# ou6_cs-base_V1_1.net
KiCad netlist of a schematic drawn in EAGLE
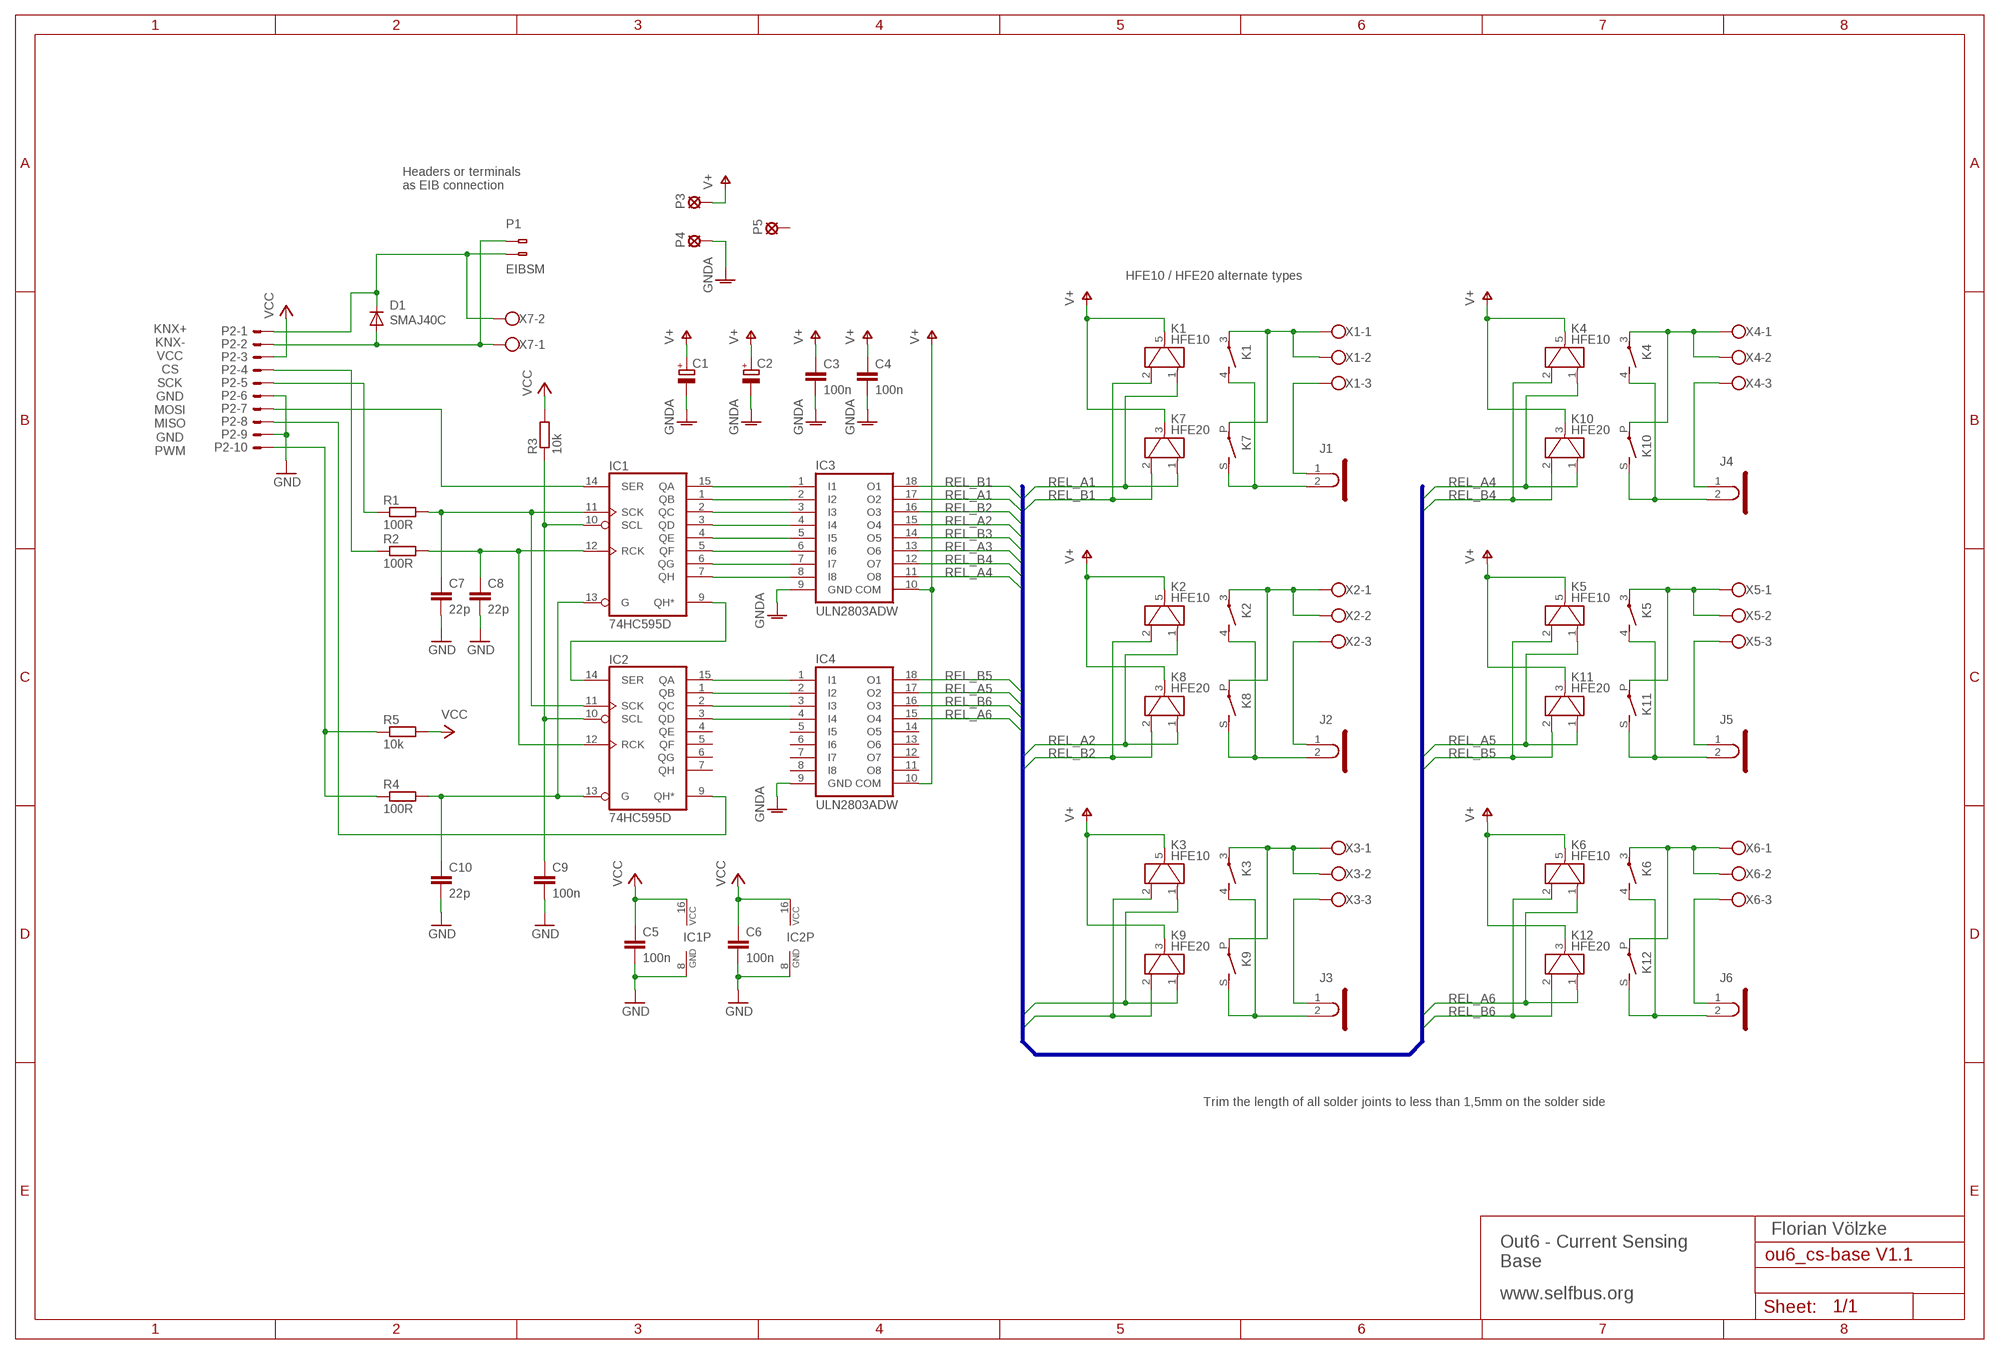
[diagram p0: schematic, sheet 1]

(export (version "E")
  (design (tool "Eeschema 10.0.6"))
  (components
    (comp (ref "C1")
      (value "CPOL-EUE5-13-20")
      (footprint "eagle-import:E5-13-20")
      (libsource (lib "eagle-import") (part "CPOL-EUE5-13-20"))
    )
    (comp (ref "C2")
      (value "CPOL-EUE5-13-20R")
      (footprint "eagle-import:E5-13-20R")
      (libsource (lib "eagle-import") (part "CPOL-EUE5-13-20R"))
    )
    (comp (ref "C3")
      (value "100n")
      (footprint "eagle-import:R0805M")
      (libsource (lib "eagle-import") (part "C-EUC0805M"))
    )
    (comp (ref "C4")
      (value "100n")
      (footprint "eagle-import:R0805M")
      (libsource (lib "eagle-import") (part "C-EUC0805M"))
    )
    (comp (ref "C5")
      (value "100n")
      (footprint "eagle-import:R0805M")
      (libsource (lib "eagle-import") (part "C-EUC0805M"))
    )
    (comp (ref "C6")
      (value "100n")
      (footprint "eagle-import:R0805M")
      (libsource (lib "eagle-import") (part "C-EUC0805M"))
    )
    (comp (ref "C7")
      (value "22p")
      (footprint "eagle-import:R0805M")
      (libsource (lib "eagle-import") (part "C-EUC0805M"))
    )
    (comp (ref "C8")
      (value "22p")
      (footprint "eagle-import:R0805M")
      (libsource (lib "eagle-import") (part "C-EUC0805M"))
    )
    (comp (ref "C9")
      (value "100n")
      (footprint "eagle-import:R0805M")
      (libsource (lib "eagle-import") (part "C-EUC0805M"))
    )
    (comp (ref "C10")
      (value "22p")
      (footprint "eagle-import:R0805M")
      (libsource (lib "eagle-import") (part "C-EUC0805M"))
    )
    (comp (ref "D1")
      (value "SMAJ40C")
      (footprint "eagle-import:SMB")
      (libsource (lib "eagle-import") (part "D-SMB"))
    )
    (comp (ref "IC1")
      (value "74HC595D")
      (footprint "eagle-import:SO16")
      (libsource (lib "eagle-import") (part "74595DHC"))
    )
    (comp (ref "IC2")
      (value "74HC595D")
      (footprint "eagle-import:SO16")
      (libsource (lib "eagle-import") (part "74595DHC"))
    )
    (comp (ref "IC3")
      (value "ULN2803ADW")
      (footprint "eagle-import:SO18W")
      (libsource (lib "eagle-import") (part "ULN2803ADW"))
    )
    (comp (ref "IC4")
      (value "ULN2803ADW")
      (footprint "eagle-import:SO18W")
      (libsource (lib "eagle-import") (part "ULN2803ADW"))
    )
    (comp (ref "J1")
      (value "IXFORMER_PRIMONLY")
      (footprint "eagle-import:IXFORMERANTIPART")
      (libsource (lib "eagle-import") (part "IXFORMER_PRIMONLY"))
    )
    (comp (ref "J2")
      (value "IXFORMER_PRIMONLY")
      (footprint "eagle-import:IXFORMERANTIPART")
      (libsource (lib "eagle-import") (part "IXFORMER_PRIMONLY"))
    )
    (comp (ref "J3")
      (value "IXFORMER_PRIMONLY")
      (footprint "eagle-import:IXFORMERANTIPART")
      (libsource (lib "eagle-import") (part "IXFORMER_PRIMONLY"))
    )
    (comp (ref "J4")
      (value "IXFORMER_PRIMONLY")
      (footprint "eagle-import:IXFORMERANTIPART")
      (libsource (lib "eagle-import") (part "IXFORMER_PRIMONLY"))
    )
    (comp (ref "J5")
      (value "IXFORMER_PRIMONLY")
      (footprint "eagle-import:IXFORMERANTIPART")
      (libsource (lib "eagle-import") (part "IXFORMER_PRIMONLY"))
    )
    (comp (ref "J6")
      (value "IXFORMER_PRIMONLY")
      (footprint "eagle-import:IXFORMERANTIPART")
      (libsource (lib "eagle-import") (part "IXFORMER_PRIMONLY"))
    )
    (comp (ref "K1")
      (value "HFE10")
      (footprint "eagle-import:PCB_REL_BIG_POWER_NO")
      (libsource (lib "eagle-import") (part "BISTABLE2C_PCB_SNGLPINHFE10"))
    )
    (comp (ref "K2")
      (value "HFE10")
      (footprint "eagle-import:PCB_REL_BIG_POWER_NO")
      (libsource (lib "eagle-import") (part "BISTABLE2C_PCB_SNGLPINHFE10"))
    )
    (comp (ref "K3")
      (value "HFE10")
      (footprint "eagle-import:PCB_REL_BIG_POWER_NO")
      (libsource (lib "eagle-import") (part "BISTABLE2C_PCB_SNGLPINHFE10"))
    )
    (comp (ref "K4")
      (value "HFE10")
      (footprint "eagle-import:PCB_REL_BIG_POWER_NO")
      (libsource (lib "eagle-import") (part "BISTABLE2C_PCB_SNGLPINHFE10"))
    )
    (comp (ref "K5")
      (value "HFE10")
      (footprint "eagle-import:PCB_REL_BIG_POWER_NO")
      (libsource (lib "eagle-import") (part "BISTABLE2C_PCB_SNGLPINHFE10"))
    )
    (comp (ref "K6")
      (value "HFE10")
      (footprint "eagle-import:PCB_REL_BIG_POWER_NO")
      (libsource (lib "eagle-import") (part "BISTABLE2C_PCB_SNGLPINHFE10"))
    )
    (comp (ref "K7")
      (value "HFE20")
      (footprint "eagle-import:PCB_REL_HP_NO_SNGLPIN")
      (libsource (lib "eagle-import") (part "BISTABLE2C_PCB_SNGLPINHFE20"))
    )
    (comp (ref "K8")
      (value "HFE20")
      (footprint "eagle-import:PCB_REL_HP_NO_SNGLPIN")
      (libsource (lib "eagle-import") (part "BISTABLE2C_PCB_SNGLPINHFE20"))
    )
    (comp (ref "K9")
      (value "HFE20")
      (footprint "eagle-import:PCB_REL_HP_NO_SNGLPIN")
      (libsource (lib "eagle-import") (part "BISTABLE2C_PCB_SNGLPINHFE20"))
    )
    (comp (ref "K10")
      (value "HFE20")
      (footprint "eagle-import:PCB_REL_HP_NO_SNGLPIN")
      (libsource (lib "eagle-import") (part "BISTABLE2C_PCB_SNGLPINHFE20"))
    )
    (comp (ref "K11")
      (value "HFE20")
      (footprint "eagle-import:PCB_REL_HP_NO_SNGLPIN")
      (libsource (lib "eagle-import") (part "BISTABLE2C_PCB_SNGLPINHFE20"))
    )
    (comp (ref "K12")
      (value "HFE20")
      (footprint "eagle-import:PCB_REL_HP_NO_SNGLPIN")
      (libsource (lib "eagle-import") (part "BISTABLE2C_PCB_SNGLPINHFE20"))
    )
    (comp (ref "P1")
      (value "EIBSM")
      (footprint "eagle-import:BUSKLEMME1_2LOECHER")
      (libsource (lib "eagle-import") (part "EIBSM"))
    )
    (comp (ref "P2")
      (value "ML10E")
      (footprint "eagle-import:ML10")
      (libsource (lib "eagle-import") (part "ML10?E"))
    )
    (comp (ref "P3")
      (value "SE1.5")
      (footprint "eagle-import:SE15")
      (libsource (lib "eagle-import") (part "SE1.5"))
    )
    (comp (ref "P4")
      (value "SE1.5")
      (footprint "eagle-import:SE15")
      (libsource (lib "eagle-import") (part "SE1.5"))
    )
    (comp (ref "P5")
      (value "SE1.5")
      (footprint "eagle-import:SE15")
      (libsource (lib "eagle-import") (part "SE1.5"))
    )
    (comp (ref "R1")
      (value "100R")
      (footprint "eagle-import:R0805M")
      (libsource (lib "eagle-import") (part "R-EU_R0805M"))
    )
    (comp (ref "R2")
      (value "100R")
      (footprint "eagle-import:R0805M")
      (libsource (lib "eagle-import") (part "R-EU_R0805M"))
    )
    (comp (ref "R3")
      (value "10k")
      (footprint "eagle-import:R0805M")
      (libsource (lib "eagle-import") (part "R-EU_R0805M"))
    )
    (comp (ref "R4")
      (value "100R")
      (footprint "eagle-import:R0805M")
      (libsource (lib "eagle-import") (part "R-EU_R0805M"))
    )
    (comp (ref "R5")
      (value "10k")
      (footprint "eagle-import:R0805M")
      (libsource (lib "eagle-import") (part "R-EU_R0805M"))
    )
    (comp (ref "X1")
      (value "KLEMME3POL5_08")
      (footprint "eagle-import:KLEMME3POL5_08")
      (libsource (lib "eagle-import") (part "KLEMME3POL5_08"))
    )
    (comp (ref "X2")
      (value "KLEMME3POL5_08")
      (footprint "eagle-import:KLEMME3POL5_08")
      (libsource (lib "eagle-import") (part "KLEMME3POL5_08"))
    )
    (comp (ref "X3")
      (value "KLEMME3POL5_08")
      (footprint "eagle-import:KLEMME3POL5_08")
      (libsource (lib "eagle-import") (part "KLEMME3POL5_08"))
    )
    (comp (ref "X4")
      (value "KLEMME3POL5_08")
      (footprint "eagle-import:KLEMME3POL5_08")
      (libsource (lib "eagle-import") (part "KLEMME3POL5_08"))
    )
    (comp (ref "X5")
      (value "KLEMME3POL5_08")
      (footprint "eagle-import:KLEMME3POL5_08")
      (libsource (lib "eagle-import") (part "KLEMME3POL5_08"))
    )
    (comp (ref "X6")
      (value "KLEMME3POL5_08")
      (footprint "eagle-import:KLEMME3POL5_08")
      (libsource (lib "eagle-import") (part "KLEMME3POL5_08"))
    )
    (comp (ref "X7")
      (value "KLEMME2POL5_08")
      (footprint "eagle-import:KLEMME2POL5_08")
      (libsource (lib "eagle-import") (part "KLEMME2POL5_08"))
    )
  )
  (nets
    (net (code "1") (name "/REL_A1") (class "Default")
      (node (ref "IC3") (pin "17") (pinfunction "O2_17") (pintype "open_collector"))
      (node (ref "K1") (pin "1") (pinfunction "3_1") (pintype "passive"))
      (node (ref "K7") (pin "1") (pinfunction "3_1") (pintype "passive"))
    )
    (net (code "2") (name "/REL_A2") (class "Default")
      (node (ref "IC3") (pin "15") (pinfunction "O4_15") (pintype "open_collector"))
      (node (ref "K2") (pin "1") (pinfunction "3_1") (pintype "passive"))
      (node (ref "K8") (pin "1") (pinfunction "3_1") (pintype "passive"))
    )
    (net (code "3") (name "/REL_A3") (class "Default")
      (node (ref "IC3") (pin "13") (pinfunction "O6_13") (pintype "open_collector"))
      (node (ref "K3") (pin "1") (pinfunction "3_1") (pintype "passive"))
      (node (ref "K9") (pin "1") (pinfunction "3_1") (pintype "passive"))
    )
    (net (code "4") (name "/REL_A4") (class "Default")
      (node (ref "IC3") (pin "11") (pinfunction "O8_11") (pintype "open_collector"))
      (node (ref "K10") (pin "1") (pinfunction "3_1") (pintype "passive"))
      (node (ref "K4") (pin "1") (pinfunction "3_1") (pintype "passive"))
    )
    (net (code "5") (name "/REL_A5") (class "Default")
      (node (ref "IC4") (pin "17") (pinfunction "O2_17") (pintype "open_collector"))
      (node (ref "K11") (pin "1") (pinfunction "3_1") (pintype "passive"))
      (node (ref "K5") (pin "1") (pinfunction "3_1") (pintype "passive"))
    )
    (net (code "6") (name "/REL_A6") (class "Default")
      (node (ref "IC4") (pin "15") (pinfunction "O4_15") (pintype "open_collector"))
      (node (ref "K12") (pin "1") (pinfunction "3_1") (pintype "passive"))
      (node (ref "K6") (pin "1") (pinfunction "3_1") (pintype "passive"))
    )
    (net (code "7") (name "/REL_B1") (class "Default")
      (node (ref "IC3") (pin "18") (pinfunction "O1_18") (pintype "open_collector"))
      (node (ref "K1") (pin "2") (pinfunction "2_2") (pintype "passive"))
      (node (ref "K7") (pin "2") (pinfunction "2_2") (pintype "passive"))
    )
    (net (code "8") (name "/REL_B2") (class "Default")
      (node (ref "IC3") (pin "16") (pinfunction "O3_16") (pintype "open_collector"))
      (node (ref "K2") (pin "2") (pinfunction "2_2") (pintype "passive"))
      (node (ref "K8") (pin "2") (pinfunction "2_2") (pintype "passive"))
    )
    (net (code "9") (name "/REL_B3") (class "Default")
      (node (ref "IC3") (pin "14") (pinfunction "O5_14") (pintype "open_collector"))
      (node (ref "K3") (pin "2") (pinfunction "2_2") (pintype "passive"))
      (node (ref "K9") (pin "2") (pinfunction "2_2") (pintype "passive"))
    )
    (net (code "10") (name "/REL_B4") (class "Default")
      (node (ref "IC3") (pin "12") (pinfunction "O7_12") (pintype "open_collector"))
      (node (ref "K10") (pin "2") (pinfunction "2_2") (pintype "passive"))
      (node (ref "K4") (pin "2") (pinfunction "2_2") (pintype "passive"))
    )
    (net (code "11") (name "/REL_B5") (class "Default")
      (node (ref "IC4") (pin "18") (pinfunction "O1_18") (pintype "open_collector"))
      (node (ref "K11") (pin "2") (pinfunction "2_2") (pintype "passive"))
      (node (ref "K5") (pin "2") (pinfunction "2_2") (pintype "passive"))
    )
    (net (code "12") (name "/REL_B6") (class "Default")
      (node (ref "IC4") (pin "16") (pinfunction "O3_16") (pintype "open_collector"))
      (node (ref "K12") (pin "2") (pinfunction "2_2") (pintype "passive"))
      (node (ref "K6") (pin "2") (pinfunction "2_2") (pintype "passive"))
    )
    (net (code "13") (name "GND") (class "Default")
      (node (ref "C10") (pin "2") (pinfunction "2_2") (pintype "passive"))
      (node (ref "C5") (pin "2") (pinfunction "2_2") (pintype "passive"))
      (node (ref "C6") (pin "2") (pinfunction "2_2") (pintype "passive"))
      (node (ref "C7") (pin "2") (pinfunction "2_2") (pintype "passive"))
      (node (ref "C8") (pin "2") (pinfunction "2_2") (pintype "passive"))
      (node (ref "C9") (pin "2") (pinfunction "2_2") (pintype "passive"))
      (node (ref "IC1") (pin "8") (pinfunction "GND_8") (pintype "power_in"))
      (node (ref "IC2") (pin "8") (pinfunction "GND_8") (pintype "power_in"))
      (node (ref "P2") (pin "6") (pinfunction "S_6") (pintype "passive"))
      (node (ref "P2") (pin "9") (pinfunction "S_9") (pintype "passive"))
    )
    (net (code "14") (name "GNDA") (class "Default")
      (node (ref "C1") (pin "-") (pinfunction "-_-") (pintype "passive"))
      (node (ref "C2") (pin "-") (pinfunction "-_-") (pintype "passive"))
      (node (ref "C3") (pin "2") (pinfunction "2_2") (pintype "passive"))
      (node (ref "C4") (pin "2") (pinfunction "2_2") (pintype "passive"))
      (node (ref "IC3") (pin "9") (pinfunction "GND_9") (pintype "power_in"))
      (node (ref "IC4") (pin "9") (pinfunction "GND_9") (pintype "power_in"))
      (node (ref "P4") (pin "MP") (pinfunction "MP_MP") (pintype "passive"))
    )
    (net (code "15") (name "Net-(D1-A)") (class "Default")
      (node (ref "D1") (pin "2") (pinfunction "A_2") (pintype "passive"))
      (node (ref "P1") (pin "1") (pinfunction "B-1_1") (pintype "passive"))
      (node (ref "P2") (pin "2") (pinfunction "S_2") (pintype "passive"))
      (node (ref "X7") (pin "P$1") (pinfunction "KL_P$1") (pintype "passive"))
    )
    (net (code "16") (name "Net-(D1-C)") (class "Default")
      (node (ref "D1") (pin "1") (pinfunction "C_1") (pintype "passive"))
      (node (ref "P1") (pin "2") (pinfunction "B-2_2") (pintype "passive"))
      (node (ref "P2") (pin "1") (pinfunction "S_1") (pintype "passive"))
      (node (ref "X7") (pin "P$2") (pinfunction "KL_P$2") (pintype "passive"))
    )
    (net (code "17") (name "Net-(IC1A-G)") (class "Default")
      (node (ref "C10") (pin "1") (pinfunction "1_1") (pintype "passive"))
      (node (ref "IC1") (pin "13") (pinfunction "G_13") (pintype "input"))
      (node (ref "IC2") (pin "13") (pinfunction "G_13") (pintype "input"))
      (node (ref "R4") (pin "2") (pinfunction "2_2") (pintype "passive"))
    )
    (net (code "18") (name "Net-(IC1A-QA)") (class "Default")
      (node (ref "IC1") (pin "15") (pinfunction "QA_15") (pintype "tri_state"))
      (node (ref "IC3") (pin "1") (pinfunction "I1_1") (pintype "input"))
    )
    (net (code "19") (name "Net-(IC1A-QB)") (class "Default")
      (node (ref "IC1") (pin "1") (pinfunction "QB_1") (pintype "tri_state"))
      (node (ref "IC3") (pin "2") (pinfunction "I2_2") (pintype "input"))
    )
    (net (code "20") (name "Net-(IC1A-QC)") (class "Default")
      (node (ref "IC1") (pin "2") (pinfunction "QC_2") (pintype "tri_state"))
      (node (ref "IC3") (pin "3") (pinfunction "I3_3") (pintype "input"))
    )
    (net (code "21") (name "Net-(IC1A-QD)") (class "Default")
      (node (ref "IC1") (pin "3") (pinfunction "QD_3") (pintype "tri_state"))
      (node (ref "IC3") (pin "4") (pinfunction "I4_4") (pintype "input"))
    )
    (net (code "22") (name "Net-(IC1A-QE)") (class "Default")
      (node (ref "IC1") (pin "4") (pinfunction "QE_4") (pintype "tri_state"))
      (node (ref "IC3") (pin "5") (pinfunction "I5_5") (pintype "input"))
    )
    (net (code "23") (name "Net-(IC1A-QF)") (class "Default")
      (node (ref "IC1") (pin "5") (pinfunction "QF_5") (pintype "tri_state"))
      (node (ref "IC3") (pin "6") (pinfunction "I6_6") (pintype "input"))
    )
    (net (code "24") (name "Net-(IC1A-QG)") (class "Default")
      (node (ref "IC1") (pin "6") (pinfunction "QG_6") (pintype "tri_state"))
      (node (ref "IC3") (pin "7") (pinfunction "I7_7") (pintype "input"))
    )
    (net (code "25") (name "Net-(IC1A-QH)") (class "Default")
      (node (ref "IC1") (pin "7") (pinfunction "QH_7") (pintype "tri_state"))
      (node (ref "IC3") (pin "8") (pinfunction "I8_8") (pintype "input"))
    )
    (net (code "26") (name "Net-(IC1A-QH*)") (class "Default")
      (node (ref "IC1") (pin "9") (pinfunction "QH*_9") (pintype "tri_state"))
      (node (ref "IC2") (pin "14") (pinfunction "SER_14") (pintype "input"))
    )
    (net (code "27") (name "Net-(IC1A-RCK)") (class "Default")
      (node (ref "C8") (pin "1") (pinfunction "1_1") (pintype "passive"))
      (node (ref "IC1") (pin "12") (pinfunction "RCK_12") (pintype "input"))
      (node (ref "IC2") (pin "12") (pinfunction "RCK_12") (pintype "input"))
      (node (ref "R2") (pin "2") (pinfunction "2_2") (pintype "passive"))
    )
    (net (code "28") (name "Net-(IC1A-SCK)") (class "Default")
      (node (ref "C7") (pin "1") (pinfunction "1_1") (pintype "passive"))
      (node (ref "IC1") (pin "11") (pinfunction "SCK_11") (pintype "input"))
      (node (ref "IC2") (pin "11") (pinfunction "SCK_11") (pintype "input"))
      (node (ref "R1") (pin "2") (pinfunction "2_2") (pintype "passive"))
    )
    (net (code "29") (name "Net-(IC1A-SCL)") (class "Default")
      (node (ref "C9") (pin "1") (pinfunction "1_1") (pintype "passive"))
      (node (ref "IC1") (pin "10") (pinfunction "SCL_10") (pintype "input"))
      (node (ref "IC2") (pin "10") (pinfunction "SCL_10") (pintype "input"))
      (node (ref "R3") (pin "1") (pinfunction "1_1") (pintype "passive"))
    )
    (net (code "30") (name "Net-(IC1A-SER)") (class "Default")
      (node (ref "IC1") (pin "14") (pinfunction "SER_14") (pintype "input"))
      (node (ref "P2") (pin "7") (pinfunction "S_7") (pintype "passive"))
    )
    (net (code "31") (name "Net-(IC2A-QA)") (class "Default")
      (node (ref "IC2") (pin "15") (pinfunction "QA_15") (pintype "tri_state"))
      (node (ref "IC4") (pin "1") (pinfunction "I1_1") (pintype "input"))
    )
    (net (code "32") (name "Net-(IC2A-QB)") (class "Default")
      (node (ref "IC2") (pin "1") (pinfunction "QB_1") (pintype "tri_state"))
      (node (ref "IC4") (pin "2") (pinfunction "I2_2") (pintype "input"))
    )
    (net (code "33") (name "Net-(IC2A-QC)") (class "Default")
      (node (ref "IC2") (pin "2") (pinfunction "QC_2") (pintype "tri_state"))
      (node (ref "IC4") (pin "3") (pinfunction "I3_3") (pintype "input"))
    )
    (net (code "34") (name "Net-(IC2A-QD)") (class "Default")
      (node (ref "IC2") (pin "3") (pinfunction "QD_3") (pintype "tri_state"))
      (node (ref "IC4") (pin "4") (pinfunction "I4_4") (pintype "input"))
    )
    (net (code "35") (name "Net-(IC2A-QH*)") (class "Default")
      (node (ref "IC2") (pin "9") (pinfunction "QH*_9") (pintype "tri_state"))
      (node (ref "P2") (pin "8") (pinfunction "S_8") (pintype "passive"))
    )
    (net (code "36") (name "Net-(K1B-P)") (class "Default")
      (node (ref "K1") (pin "3") (pinfunction "P_3") (pintype "passive"))
      (node (ref "K7") (pin "P") (pinfunction "P_P") (pintype "passive"))
      (node (ref "X1") (pin "P$1") (pinfunction "KL_P$1") (pintype "passive"))
      (node (ref "X1") (pin "P$2") (pinfunction "KL_P$2") (pintype "passive"))
    )
    (net (code "37") (name "Net-(K1B-S)") (class "Default")
      (node (ref "J1") (pin "2") (pinfunction "2_2") (pintype "passive"))
      (node (ref "K1") (pin "4") (pinfunction "S_4") (pintype "passive"))
      (node (ref "K7") (pin "S") (pinfunction "S_S") (pintype "passive"))
    )
    (net (code "38") (name "Net-(K2B-P)") (class "Default")
      (node (ref "K2") (pin "3") (pinfunction "P_3") (pintype "passive"))
      (node (ref "K8") (pin "P") (pinfunction "P_P") (pintype "passive"))
      (node (ref "X2") (pin "P$1") (pinfunction "KL_P$1") (pintype "passive"))
      (node (ref "X2") (pin "P$2") (pinfunction "KL_P$2") (pintype "passive"))
    )
    (net (code "39") (name "Net-(K2B-S)") (class "Default")
      (node (ref "J2") (pin "2") (pinfunction "2_2") (pintype "passive"))
      (node (ref "K2") (pin "4") (pinfunction "S_4") (pintype "passive"))
      (node (ref "K8") (pin "S") (pinfunction "S_S") (pintype "passive"))
    )
    (net (code "40") (name "Net-(K3B-P)") (class "Default")
      (node (ref "K3") (pin "3") (pinfunction "P_3") (pintype "passive"))
      (node (ref "K9") (pin "P") (pinfunction "P_P") (pintype "passive"))
      (node (ref "X3") (pin "P$1") (pinfunction "KL_P$1") (pintype "passive"))
      (node (ref "X3") (pin "P$2") (pinfunction "KL_P$2") (pintype "passive"))
    )
    (net (code "41") (name "Net-(K3B-S)") (class "Default")
      (node (ref "J3") (pin "2") (pinfunction "2_2") (pintype "passive"))
      (node (ref "K3") (pin "4") (pinfunction "S_4") (pintype "passive"))
      (node (ref "K9") (pin "S") (pinfunction "S_S") (pintype "passive"))
    )
    (net (code "42") (name "Net-(K4B-P)") (class "Default")
      (node (ref "K10") (pin "P") (pinfunction "P_P") (pintype "passive"))
      (node (ref "K4") (pin "3") (pinfunction "P_3") (pintype "passive"))
      (node (ref "X4") (pin "P$1") (pinfunction "KL_P$1") (pintype "passive"))
      (node (ref "X4") (pin "P$2") (pinfunction "KL_P$2") (pintype "passive"))
    )
    (net (code "43") (name "Net-(K4B-S)") (class "Default")
      (node (ref "J4") (pin "2") (pinfunction "2_2") (pintype "passive"))
      (node (ref "K10") (pin "S") (pinfunction "S_S") (pintype "passive"))
      (node (ref "K4") (pin "4") (pinfunction "S_4") (pintype "passive"))
    )
    (net (code "44") (name "Net-(K5B-P)") (class "Default")
      (node (ref "K11") (pin "P") (pinfunction "P_P") (pintype "passive"))
      (node (ref "K5") (pin "3") (pinfunction "P_3") (pintype "passive"))
      (node (ref "X5") (pin "P$1") (pinfunction "KL_P$1") (pintype "passive"))
      (node (ref "X5") (pin "P$2") (pinfunction "KL_P$2") (pintype "passive"))
    )
    (net (code "45") (name "Net-(K5B-S)") (class "Default")
      (node (ref "J5") (pin "2") (pinfunction "2_2") (pintype "passive"))
      (node (ref "K11") (pin "S") (pinfunction "S_S") (pintype "passive"))
      (node (ref "K5") (pin "4") (pinfunction "S_4") (pintype "passive"))
    )
    (net (code "46") (name "Net-(K6B-P)") (class "Default")
      (node (ref "K12") (pin "P") (pinfunction "P_P") (pintype "passive"))
      (node (ref "K6") (pin "3") (pinfunction "P_3") (pintype "passive"))
      (node (ref "X6") (pin "P$1") (pinfunction "KL_P$1") (pintype "passive"))
      (node (ref "X6") (pin "P$2") (pinfunction "KL_P$2") (pintype "passive"))
    )
    (net (code "47") (name "Net-(K6B-S)") (class "Default")
      (node (ref "J6") (pin "2") (pinfunction "2_2") (pintype "passive"))
      (node (ref "K12") (pin "S") (pinfunction "S_S") (pintype "passive"))
      (node (ref "K6") (pin "4") (pinfunction "S_4") (pintype "passive"))
    )
    (net (code "48") (name "Net-(P2B-S)") (class "Default")
      (node (ref "P2") (pin "10") (pinfunction "S_10") (pintype "passive"))
      (node (ref "R4") (pin "1") (pinfunction "1_1") (pintype "passive"))
      (node (ref "R5") (pin "1") (pinfunction "1_1") (pintype "passive"))
    )
    (net (code "49") (name "Net-(P2E-S)") (class "Default")
      (node (ref "P2") (pin "4") (pinfunction "S_4") (pintype "passive"))
      (node (ref "R2") (pin "1") (pinfunction "1_1") (pintype "passive"))
    )
    (net (code "50") (name "Net-(P2F-S)") (class "Default")
      (node (ref "P2") (pin "5") (pinfunction "S_5") (pintype "passive"))
      (node (ref "R1") (pin "1") (pinfunction "1_1") (pintype "passive"))
    )
    (net (code "51") (name "Net-(X1C-KL)") (class "Default")
      (node (ref "J1") (pin "1") (pinfunction "1_1") (pintype "passive"))
      (node (ref "X1") (pin "P$3") (pinfunction "KL_P$3") (pintype "passive"))
    )
    (net (code "52") (name "Net-(X2C-KL)") (class "Default")
      (node (ref "J2") (pin "1") (pinfunction "1_1") (pintype "passive"))
      (node (ref "X2") (pin "P$3") (pinfunction "KL_P$3") (pintype "passive"))
    )
    (net (code "53") (name "Net-(X3C-KL)") (class "Default")
      (node (ref "J3") (pin "1") (pinfunction "1_1") (pintype "passive"))
      (node (ref "X3") (pin "P$3") (pinfunction "KL_P$3") (pintype "passive"))
    )
    (net (code "54") (name "Net-(X4C-KL)") (class "Default")
      (node (ref "J4") (pin "1") (pinfunction "1_1") (pintype "passive"))
      (node (ref "X4") (pin "P$3") (pinfunction "KL_P$3") (pintype "passive"))
    )
    (net (code "55") (name "Net-(X5C-KL)") (class "Default")
      (node (ref "J5") (pin "1") (pinfunction "1_1") (pintype "passive"))
      (node (ref "X5") (pin "P$3") (pinfunction "KL_P$3") (pintype "passive"))
    )
    (net (code "56") (name "Net-(X6C-KL)") (class "Default")
      (node (ref "J6") (pin "1") (pinfunction "1_1") (pintype "passive"))
      (node (ref "X6") (pin "P$3") (pinfunction "KL_P$3") (pintype "passive"))
    )
    (net (code "57") (name "V+") (class "Default")
      (node (ref "C1") (pin "+") (pinfunction "+_+") (pintype "passive"))
      (node (ref "C2") (pin "+") (pinfunction "+_+") (pintype "passive"))
      (node (ref "C3") (pin "1") (pinfunction "1_1") (pintype "passive"))
      (node (ref "C4") (pin "1") (pinfunction "1_1") (pintype "passive"))
      (node (ref "IC3") (pin "10") (pinfunction "COM_10") (pintype "passive"))
      (node (ref "IC4") (pin "10") (pinfunction "COM_10") (pintype "passive"))
      (node (ref "K1") (pin "5") (pinfunction "1_5") (pintype "passive"))
      (node (ref "K10") (pin "3") (pinfunction "1_3") (pintype "passive"))
      (node (ref "K11") (pin "3") (pinfunction "1_3") (pintype "passive"))
      (node (ref "K12") (pin "3") (pinfunction "1_3") (pintype "passive"))
      (node (ref "K2") (pin "5") (pinfunction "1_5") (pintype "passive"))
      (node (ref "K3") (pin "5") (pinfunction "1_5") (pintype "passive"))
      (node (ref "K4") (pin "5") (pinfunction "1_5") (pintype "passive"))
      (node (ref "K5") (pin "5") (pinfunction "1_5") (pintype "passive"))
      (node (ref "K6") (pin "5") (pinfunction "1_5") (pintype "passive"))
      (node (ref "K7") (pin "3") (pinfunction "1_3") (pintype "passive"))
      (node (ref "K8") (pin "3") (pinfunction "1_3") (pintype "passive"))
      (node (ref "K9") (pin "3") (pinfunction "1_3") (pintype "passive"))
      (node (ref "P3") (pin "MP") (pinfunction "MP_MP") (pintype "passive"))
    )
    (net (code "58") (name "VCC") (class "Default")
      (node (ref "C5") (pin "1") (pinfunction "1_1") (pintype "passive"))
      (node (ref "C6") (pin "1") (pinfunction "1_1") (pintype "passive"))
      (node (ref "IC1") (pin "16") (pinfunction "VCC_16") (pintype "power_in"))
      (node (ref "IC2") (pin "16") (pinfunction "VCC_16") (pintype "power_in"))
      (node (ref "P2") (pin "3") (pinfunction "S_3") (pintype "passive"))
      (node (ref "R3") (pin "2") (pinfunction "2_2") (pintype "passive"))
      (node (ref "R5") (pin "2") (pinfunction "2_2") (pintype "passive"))
    )
    (net (code "59") (name "unconnected-(IC2A-QE-Pad4)") (class "Default")
      (node (ref "IC2") (pin "4") (pinfunction "QE_4") (pintype "tri_state"))
    )
    (net (code "60") (name "unconnected-(IC2A-QF-Pad5)") (class "Default")
      (node (ref "IC2") (pin "5") (pinfunction "QF_5") (pintype "tri_state"))
    )
    (net (code "61") (name "unconnected-(IC2A-QG-Pad6)") (class "Default")
      (node (ref "IC2") (pin "6") (pinfunction "QG_6") (pintype "tri_state"))
    )
    (net (code "62") (name "unconnected-(IC2A-QH-Pad7)") (class "Default")
      (node (ref "IC2") (pin "7") (pinfunction "QH_7") (pintype "tri_state"))
    )
    (net (code "63") (name "unconnected-(IC4-I5-Pad5)") (class "Default")
      (node (ref "IC4") (pin "5") (pinfunction "I5_5") (pintype "input"))
    )
    (net (code "64") (name "unconnected-(IC4-I6-Pad6)") (class "Default")
      (node (ref "IC4") (pin "6") (pinfunction "I6_6") (pintype "input"))
    )
    (net (code "65") (name "unconnected-(IC4-I7-Pad7)") (class "Default")
      (node (ref "IC4") (pin "7") (pinfunction "I7_7") (pintype "input"))
    )
    (net (code "66") (name "unconnected-(IC4-I8-Pad8)") (class "Default")
      (node (ref "IC4") (pin "8") (pinfunction "I8_8") (pintype "input"))
    )
    (net (code "67") (name "unconnected-(IC4-O5-Pad14)") (class "Default")
      (node (ref "IC4") (pin "14") (pinfunction "O5_14") (pintype "open_collector"))
    )
    (net (code "68") (name "unconnected-(IC4-O6-Pad13)") (class "Default")
      (node (ref "IC4") (pin "13") (pinfunction "O6_13") (pintype "open_collector"))
    )
    (net (code "69") (name "unconnected-(IC4-O7-Pad12)") (class "Default")
      (node (ref "IC4") (pin "12") (pinfunction "O7_12") (pintype "open_collector"))
    )
    (net (code "70") (name "unconnected-(IC4-O8-Pad11)") (class "Default")
      (node (ref "IC4") (pin "11") (pinfunction "O8_11") (pintype "open_collector"))
    )
    (net (code "71") (name "unconnected-(P5-PadMP)") (class "Default")
      (node (ref "P5") (pin "MP") (pinfunction "MP_MP") (pintype "passive"))
    )
  )
)
